# SCH_Token_Function.net
KiCad netlist of a schematic drawn in EasyEDA
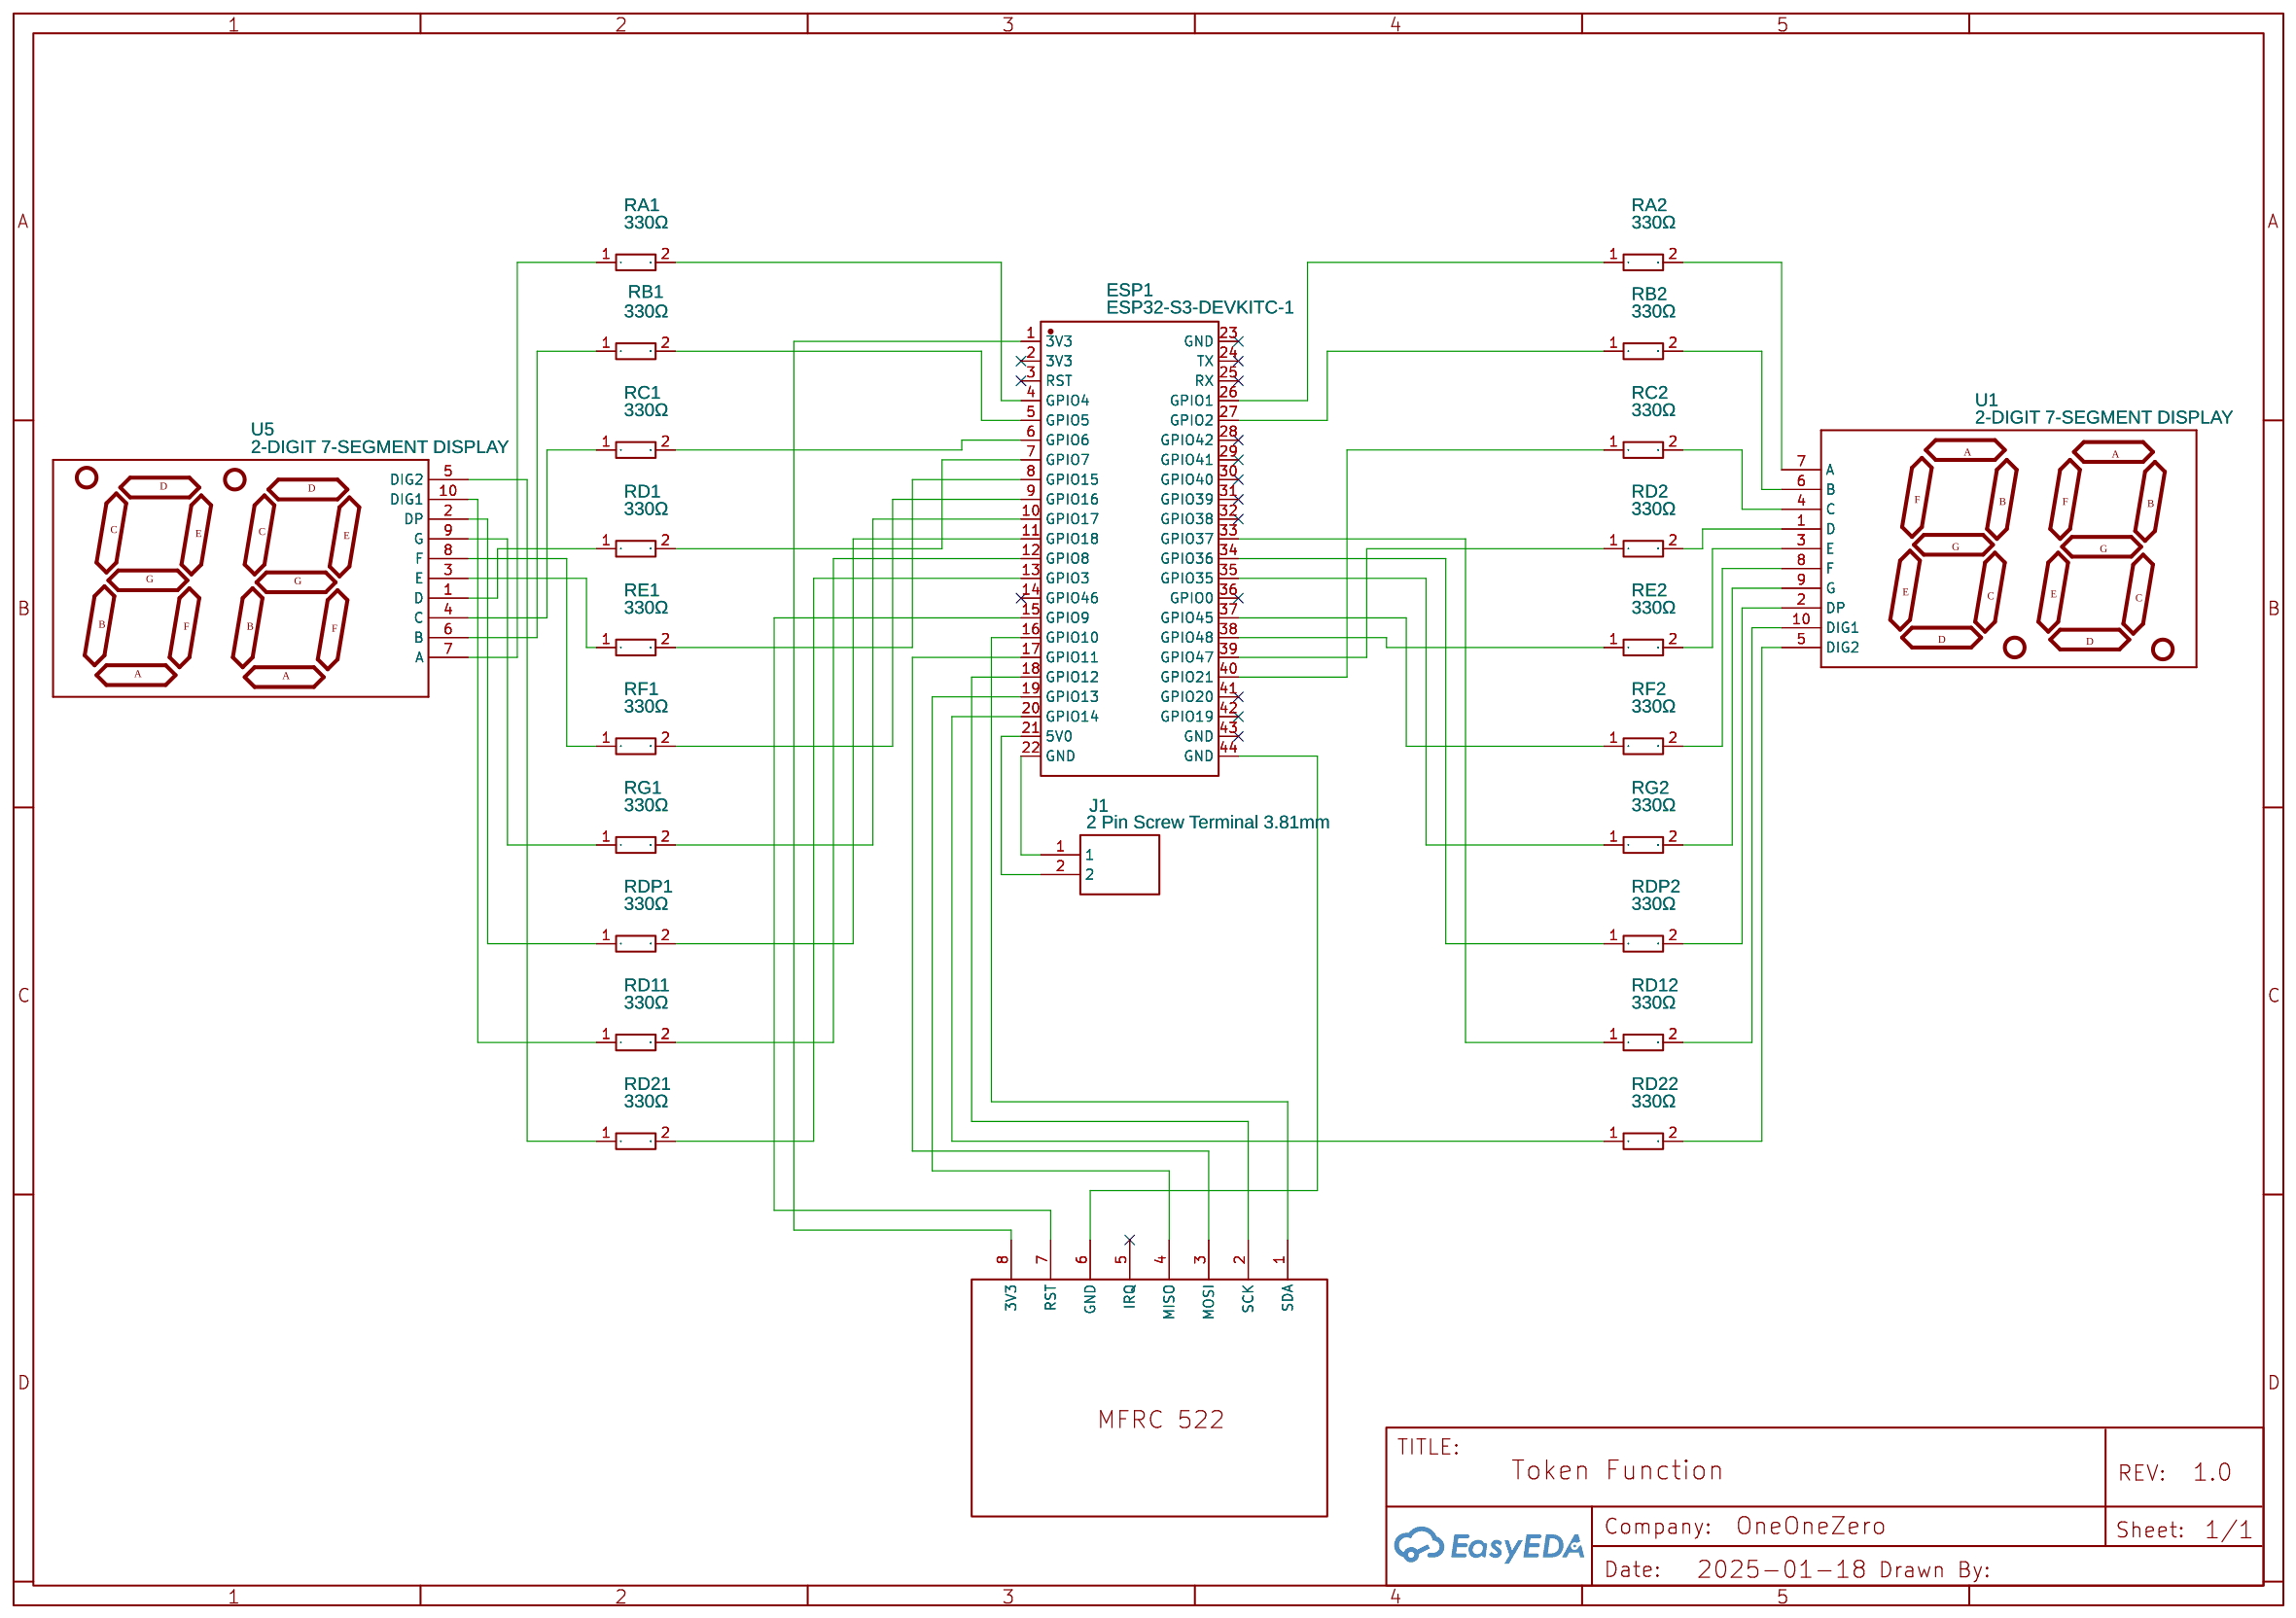
[diagram p0: schematic sheet]

(export (version "E")
  (design (tool "Eeschema 10.0.6"))
  (components
    (comp (ref "ESP1") (value "ESP32-S3-DEVKITC-1") (libsource (lib "") (part "ESP32-S3-DEVKITC-1")))
    (comp (ref "J1")
      (value "2 Pin Screw Terminal 3.81mm")
      (libsource (lib "") (part "2 Pin Screw Terminal 3.81mm"))
    )
    (comp (ref "RA1")
      (value "330Ω")
      (fields (field (name "Manufacturer Part") "MF1/4W-330Ω±1% T") (field (name "Manufacturer") "CCO(千志电子)"))
      (libsource (lib "") (part "V2-330Ω-THROUGH-HOLE-RESISTORS-5%-1/4W-D2.3-L6.5MM_3"))
    )
    (comp (ref "RA2")
      (value "330Ω")
      (fields (field (name "Manufacturer Part") "MF1/4W-330Ω±1% T") (field (name "Manufacturer") "CCO(千志电子)"))
      (libsource (lib "") (part "V2-330Ω-THROUGH-HOLE-RESISTORS-5%-1/4W-D2.3-L6.5MM_3"))
    )
    (comp (ref "RB1")
      (value "330Ω")
      (fields (field (name "Manufacturer Part") "MF1/4W-330Ω±1% T") (field (name "Manufacturer") "CCO(千志电子)"))
      (libsource (lib "") (part "V2-330Ω-THROUGH-HOLE-RESISTORS-5%-1/4W-D2.3-L6.5MM_6"))
    )
    (comp (ref "RB2")
      (value "330Ω")
      (fields (field (name "Manufacturer Part") "MF1/4W-330Ω±1% T") (field (name "Manufacturer") "CCO(千志电子)"))
      (libsource (lib "") (part "V2-330Ω-THROUGH-HOLE-RESISTORS-5%-1/4W-D2.3-L6.5MM_6"))
    )
    (comp (ref "RC1")
      (value "330Ω")
      (fields (field (name "Manufacturer Part") "MF1/4W-330Ω±1% T") (field (name "Manufacturer") "CCO(千志电子)"))
      (libsource (lib "") (part "V2-330Ω-THROUGH-HOLE-RESISTORS-5%-1/4W-D2.3-L6.5MM_5"))
    )
    (comp (ref "RC2")
      (value "330Ω")
      (fields (field (name "Manufacturer Part") "MF1/4W-330Ω±1% T") (field (name "Manufacturer") "CCO(千志电子)"))
      (libsource (lib "") (part "V2-330Ω-THROUGH-HOLE-RESISTORS-5%-1/4W-D2.3-L6.5MM_5"))
    )
    (comp (ref "RD1")
      (value "330Ω")
      (fields (field (name "Manufacturer Part") "MF1/4W-330Ω±1% T") (field (name "Manufacturer") "CCO(千志电子)"))
      (libsource (lib "") (part "V2-330Ω-THROUGH-HOLE-RESISTORS-5%-1/4W-D2.3-L6.5MM_2"))
    )
    (comp (ref "RD2")
      (value "330Ω")
      (fields (field (name "Manufacturer Part") "MF1/4W-330Ω±1% T") (field (name "Manufacturer") "CCO(千志电子)"))
      (libsource (lib "") (part "V2-330Ω-THROUGH-HOLE-RESISTORS-5%-1/4W-D2.3-L6.5MM_2"))
    )
    (comp (ref "RD11")
      (value "330Ω")
      (fields (field (name "Manufacturer Part") "MF1/4W-330Ω±1% T") (field (name "Manufacturer") "CCO(千志电子)"))
      (libsource (lib "") (part "V2-330Ω-THROUGH-HOLE-RESISTORS-5%-1/4W-D2.3-L6.5MM_2"))
    )
    (comp (ref "RD12")
      (value "330Ω")
      (fields (field (name "Manufacturer Part") "MF1/4W-330Ω±1% T") (field (name "Manufacturer") "CCO(千志电子)"))
      (libsource (lib "") (part "V2-330Ω-THROUGH-HOLE-RESISTORS-5%-1/4W-D2.3-L6.5MM_2"))
    )
    (comp (ref "RD21")
      (value "330Ω")
      (fields (field (name "Manufacturer Part") "MF1/4W-330Ω±1% T") (field (name "Manufacturer") "CCO(千志电子)"))
      (libsource (lib "") (part "V2-330Ω-THROUGH-HOLE-RESISTORS-5%-1/4W-D2.3-L6.5MM_2"))
    )
    (comp (ref "RD22")
      (value "330Ω")
      (fields (field (name "Manufacturer Part") "MF1/4W-330Ω±1% T") (field (name "Manufacturer") "CCO(千志电子)"))
      (libsource (lib "") (part "V2-330Ω-THROUGH-HOLE-RESISTORS-5%-1/4W-D2.3-L6.5MM_2"))
    )
    (comp (ref "RDP1")
      (value "330Ω")
      (fields (field (name "Manufacturer Part") "MF1/4W-330Ω±1% T") (field (name "Manufacturer") "CCO(千志电子)"))
      (libsource (lib "") (part "V2-330Ω-THROUGH-HOLE-RESISTORS-5%-1/4W-D2.3-L6.5MM_7"))
    )
    (comp (ref "RDP2")
      (value "330Ω")
      (fields (field (name "Manufacturer Part") "MF1/4W-330Ω±1% T") (field (name "Manufacturer") "CCO(千志电子)"))
      (libsource (lib "") (part "V2-330Ω-THROUGH-HOLE-RESISTORS-5%-1/4W-D2.3-L6.5MM_7"))
    )
    (comp (ref "RE1")
      (value "330Ω")
      (fields (field (name "Manufacturer Part") "MF1/4W-330Ω±1% T") (field (name "Manufacturer") "CCO(千志电子)"))
      (libsource (lib "") (part "V2-330Ω-THROUGH-HOLE-RESISTORS-5%-1/4W-D2.3-L6.5MM_4"))
    )
    (comp (ref "RE2")
      (value "330Ω")
      (fields (field (name "Manufacturer Part") "MF1/4W-330Ω±1% T") (field (name "Manufacturer") "CCO(千志电子)"))
      (libsource (lib "") (part "V2-330Ω-THROUGH-HOLE-RESISTORS-5%-1/4W-D2.3-L6.5MM_4"))
    )
    (comp (ref "RF1")
      (value "330Ω")
      (fields (field (name "Manufacturer Part") "MF1/4W-330Ω±1% T") (field (name "Manufacturer") "CCO(千志电子)"))
      (libsource (lib "") (part "V2-330Ω-THROUGH-HOLE-RESISTORS-5%-1/4W-D2.3-L6.5MM"))
    )
    (comp (ref "RF2")
      (value "330Ω")
      (fields (field (name "Manufacturer Part") "MF1/4W-330Ω±1% T") (field (name "Manufacturer") "CCO(千志电子)"))
      (libsource (lib "") (part "V2-330Ω-THROUGH-HOLE-RESISTORS-5%-1/4W-D2.3-L6.5MM"))
    )
    (comp (ref "RG1")
      (value "330Ω")
      (fields (field (name "Manufacturer Part") "MF1/4W-330Ω±1% T") (field (name "Manufacturer") "CCO(千志电子)"))
      (libsource (lib "") (part "V2-330Ω-THROUGH-HOLE-RESISTORS-5%-1/4W-D2.3-L6.5MM_1"))
    )
    (comp (ref "RG2")
      (value "330Ω")
      (fields (field (name "Manufacturer Part") "MF1/4W-330Ω±1% T") (field (name "Manufacturer") "CCO(千志电子)"))
      (libsource (lib "") (part "V2-330Ω-THROUGH-HOLE-RESISTORS-5%-1/4W-D2.3-L6.5MM_1"))
    )
    (comp (ref "U1")
      (value "2-DIGIT 7-SEGMENT DISPLAY")
      (libsource (lib "") (part "2-DIGIT 7-SEGMENT DISPLAY"))
    )
    (comp (ref "U2") (value "MFRC522-MODULE-FLIPPED") (libsource (lib "") (part "MFRC522-MODULE-FLIPPED")))
    (comp (ref "U5")
      (value "2-DIGIT 7-SEGMENT DISPLAY")
      (libsource (lib "") (part "2-DIGIT 7-SEGMENT DISPLAY_1"))
    )
  )
  (nets
    (net (code "1") (name "Net-(ESP1-5V0)") (class "Default")
      (node (ref "ESP1") (pin "21") (pinfunction "5V0_21") (pintype "unspecified"))
      (node (ref "J1") (pin "2") (pinfunction "2_2") (pintype "unspecified"))
    )
    (net (code "2") (name "Net-(ESP1-GND-Pad22)") (class "Default")
      (node (ref "ESP1") (pin "22") (pinfunction "GND_22") (pintype "unspecified"))
      (node (ref "J1") (pin "1") (pinfunction "1_1") (pintype "unspecified"))
    )
    (net (code "3") (name "Net-(ESP1-GPIO1)") (class "Default")
      (node (ref "ESP1") (pin "26") (pinfunction "GPIO1_26") (pintype "unspecified"))
      (node (ref "RA2") (pin "1") (pinfunction "1_1") (pintype "unspecified"))
    )
    (net (code "4") (name "Net-(ESP1-GPIO2)") (class "Default")
      (node (ref "ESP1") (pin "27") (pinfunction "GPIO2_27") (pintype "unspecified"))
      (node (ref "RB2") (pin "1") (pinfunction "1_1") (pintype "unspecified"))
    )
    (net (code "5") (name "Net-(ESP1-GPIO3)") (class "Default")
      (node (ref "ESP1") (pin "13") (pinfunction "GPIO3_13") (pintype "unspecified"))
      (node (ref "RD21") (pin "2") (pinfunction "2_2") (pintype "unspecified"))
    )
    (net (code "6") (name "Net-(ESP1-GPIO4)") (class "Default")
      (node (ref "ESP1") (pin "4") (pinfunction "GPIO4_4") (pintype "unspecified"))
      (node (ref "RA1") (pin "2") (pinfunction "2_2") (pintype "unspecified"))
    )
    (net (code "7") (name "Net-(ESP1-GPIO5)") (class "Default")
      (node (ref "ESP1") (pin "5") (pinfunction "GPIO5_5") (pintype "unspecified"))
      (node (ref "RB1") (pin "2") (pinfunction "2_2") (pintype "unspecified"))
    )
    (net (code "8") (name "Net-(ESP1-GPIO6)") (class "Default")
      (node (ref "ESP1") (pin "6") (pinfunction "GPIO6_6") (pintype "unspecified"))
      (node (ref "RC1") (pin "2") (pinfunction "2_2") (pintype "unspecified"))
    )
    (net (code "9") (name "Net-(ESP1-GPIO7)") (class "Default")
      (node (ref "ESP1") (pin "7") (pinfunction "GPIO7_7") (pintype "unspecified"))
      (node (ref "RD1") (pin "2") (pinfunction "2_2") (pintype "unspecified"))
    )
    (net (code "10") (name "Net-(ESP1-GPIO8)") (class "Default")
      (node (ref "ESP1") (pin "12") (pinfunction "GPIO8_12") (pintype "unspecified"))
      (node (ref "RD11") (pin "2") (pinfunction "2_2") (pintype "unspecified"))
    )
    (net (code "11") (name "Net-(ESP1-GPIO9)") (class "Default")
      (node (ref "ESP1") (pin "15") (pinfunction "GPIO9_15") (pintype "unspecified"))
      (node (ref "U2") (pin "7") (pinfunction "RST_7") (pintype "unspecified"))
    )
    (net (code "12") (name "Net-(ESP1-GPIO10)") (class "Default")
      (node (ref "ESP1") (pin "16") (pinfunction "GPIO10_16") (pintype "unspecified"))
      (node (ref "U2") (pin "1") (pinfunction "SDA_1") (pintype "unspecified"))
    )
    (net (code "13") (name "Net-(ESP1-GPIO11)") (class "Default")
      (node (ref "ESP1") (pin "17") (pinfunction "GPIO11_17") (pintype "unspecified"))
      (node (ref "U2") (pin "3") (pinfunction "MOSI_3") (pintype "unspecified"))
    )
    (net (code "14") (name "Net-(ESP1-GPIO12)") (class "Default")
      (node (ref "ESP1") (pin "18") (pinfunction "GPIO12_18") (pintype "unspecified"))
      (node (ref "U2") (pin "2") (pinfunction "SCK_2") (pintype "unspecified"))
    )
    (net (code "15") (name "Net-(ESP1-GPIO13)") (class "Default")
      (node (ref "ESP1") (pin "19") (pinfunction "GPIO13_19") (pintype "unspecified"))
      (node (ref "U2") (pin "4") (pinfunction "MISO_4") (pintype "unspecified"))
    )
    (net (code "16") (name "Net-(ESP1-GPIO14)") (class "Default")
      (node (ref "ESP1") (pin "20") (pinfunction "GPIO14_20") (pintype "unspecified"))
      (node (ref "RD22") (pin "1") (pinfunction "1_1") (pintype "unspecified"))
    )
    (net (code "17") (name "Net-(ESP1-GPIO15)") (class "Default")
      (node (ref "ESP1") (pin "8") (pinfunction "GPIO15_8") (pintype "unspecified"))
      (node (ref "RE1") (pin "2") (pinfunction "2_2") (pintype "unspecified"))
    )
    (net (code "18") (name "Net-(ESP1-GPIO16)") (class "Default")
      (node (ref "ESP1") (pin "9") (pinfunction "GPIO16_9") (pintype "unspecified"))
      (node (ref "RF1") (pin "2") (pinfunction "2_2") (pintype "unspecified"))
    )
    (net (code "19") (name "Net-(ESP1-GPIO17)") (class "Default")
      (node (ref "ESP1") (pin "10") (pinfunction "GPIO17_10") (pintype "unspecified"))
      (node (ref "RG1") (pin "2") (pinfunction "2_2") (pintype "unspecified"))
    )
    (net (code "20") (name "Net-(ESP1-GPIO18)") (class "Default")
      (node (ref "ESP1") (pin "11") (pinfunction "GPIO18_11") (pintype "unspecified"))
      (node (ref "RDP1") (pin "2") (pinfunction "2_2") (pintype "unspecified"))
    )
    (net (code "21") (name "Net-(ESP1-GPIO21)") (class "Default")
      (node (ref "ESP1") (pin "40") (pinfunction "GPIO21_40") (pintype "unspecified"))
      (node (ref "RC2") (pin "1") (pinfunction "1_1") (pintype "unspecified"))
    )
    (net (code "22") (name "Net-(ESP1-GPIO35)") (class "Default")
      (node (ref "ESP1") (pin "35") (pinfunction "GPIO35_35") (pintype "unspecified"))
      (node (ref "RG2") (pin "1") (pinfunction "1_1") (pintype "unspecified"))
    )
    (net (code "23") (name "Net-(ESP1-GPIO36)") (class "Default")
      (node (ref "ESP1") (pin "34") (pinfunction "GPIO36_34") (pintype "unspecified"))
      (node (ref "RDP2") (pin "1") (pinfunction "1_1") (pintype "unspecified"))
    )
    (net (code "24") (name "Net-(ESP1-GPIO37)") (class "Default")
      (node (ref "ESP1") (pin "33") (pinfunction "GPIO37_33") (pintype "unspecified"))
      (node (ref "RD12") (pin "1") (pinfunction "1_1") (pintype "unspecified"))
    )
    (net (code "25") (name "Net-(ESP1-GPIO45)") (class "Default")
      (node (ref "ESP1") (pin "37") (pinfunction "GPIO45_37") (pintype "unspecified"))
      (node (ref "RF2") (pin "1") (pinfunction "1_1") (pintype "unspecified"))
    )
    (net (code "26") (name "Net-(ESP1-GPIO47)") (class "Default")
      (node (ref "ESP1") (pin "39") (pinfunction "GPIO47_39") (pintype "unspecified"))
      (node (ref "RD2") (pin "1") (pinfunction "1_1") (pintype "unspecified"))
    )
    (net (code "27") (name "Net-(ESP1-GPIO48)") (class "Default")
      (node (ref "ESP1") (pin "38") (pinfunction "GPIO48_38") (pintype "unspecified"))
      (node (ref "RE2") (pin "1") (pinfunction "1_1") (pintype "unspecified"))
    )
    (net (code "28") (name "Net-(U1-A)") (class "Default")
      (node (ref "RA2") (pin "2") (pinfunction "2_2") (pintype "unspecified"))
      (node (ref "U1") (pin "7") (pinfunction "A_7") (pintype "unspecified"))
    )
    (net (code "29") (name "Net-(U1-B)") (class "Default")
      (node (ref "RB2") (pin "2") (pinfunction "2_2") (pintype "unspecified"))
      (node (ref "U1") (pin "6") (pinfunction "B_6") (pintype "unspecified"))
    )
    (net (code "30") (name "Net-(U1-C)") (class "Default")
      (node (ref "RC2") (pin "2") (pinfunction "2_2") (pintype "unspecified"))
      (node (ref "U1") (pin "4") (pinfunction "C_4") (pintype "unspecified"))
    )
    (net (code "31") (name "Net-(U1-D)") (class "Default")
      (node (ref "RD2") (pin "2") (pinfunction "2_2") (pintype "unspecified"))
      (node (ref "U1") (pin "1") (pinfunction "D_1") (pintype "unspecified"))
    )
    (net (code "32") (name "Net-(U1-DIG1)") (class "Default")
      (node (ref "RD12") (pin "2") (pinfunction "2_2") (pintype "unspecified"))
      (node (ref "U1") (pin "10") (pinfunction "DIG1_10") (pintype "unspecified"))
    )
    (net (code "33") (name "Net-(U1-DIG2)") (class "Default")
      (node (ref "RD22") (pin "2") (pinfunction "2_2") (pintype "unspecified"))
      (node (ref "U1") (pin "5") (pinfunction "DIG2_5") (pintype "unspecified"))
    )
    (net (code "34") (name "Net-(U1-DP)") (class "Default")
      (node (ref "RDP2") (pin "2") (pinfunction "2_2") (pintype "unspecified"))
      (node (ref "U1") (pin "2") (pinfunction "DP_2") (pintype "unspecified"))
    )
    (net (code "35") (name "Net-(U1-E)") (class "Default")
      (node (ref "RE2") (pin "2") (pinfunction "2_2") (pintype "unspecified"))
      (node (ref "U1") (pin "3") (pinfunction "E_3") (pintype "unspecified"))
    )
    (net (code "36") (name "Net-(U1-F)") (class "Default")
      (node (ref "RF2") (pin "2") (pinfunction "2_2") (pintype "unspecified"))
      (node (ref "U1") (pin "8") (pinfunction "F_8") (pintype "unspecified"))
    )
    (net (code "37") (name "Net-(U1-G)") (class "Default")
      (node (ref "RG2") (pin "2") (pinfunction "2_2") (pintype "unspecified"))
      (node (ref "U1") (pin "9") (pinfunction "G_9") (pintype "unspecified"))
    )
    (net (code "38") (name "Net-(U2-3V3)") (class "Default")
      (node (ref "ESP1") (pin "1") (pinfunction "3V3_1") (pintype "unspecified"))
      (node (ref "U2") (pin "8") (pinfunction "3V3_8") (pintype "unspecified"))
    )
    (net (code "39") (name "Net-(U2-GND)") (class "Default")
      (node (ref "ESP1") (pin "44") (pinfunction "GND_44") (pintype "unspecified"))
      (node (ref "U2") (pin "6") (pinfunction "GND_6") (pintype "unspecified"))
    )
    (net (code "40") (name "Net-(U5-A)") (class "Default")
      (node (ref "RA1") (pin "1") (pinfunction "1_1") (pintype "unspecified"))
      (node (ref "U5") (pin "7") (pinfunction "A_7") (pintype "unspecified"))
    )
    (net (code "41") (name "Net-(U5-B)") (class "Default")
      (node (ref "RB1") (pin "1") (pinfunction "1_1") (pintype "unspecified"))
      (node (ref "U5") (pin "6") (pinfunction "B_6") (pintype "unspecified"))
    )
    (net (code "42") (name "Net-(U5-C)") (class "Default")
      (node (ref "RC1") (pin "1") (pinfunction "1_1") (pintype "unspecified"))
      (node (ref "U5") (pin "4") (pinfunction "C_4") (pintype "unspecified"))
    )
    (net (code "43") (name "Net-(U5-D)") (class "Default")
      (node (ref "RD1") (pin "1") (pinfunction "1_1") (pintype "unspecified"))
      (node (ref "U5") (pin "1") (pinfunction "D_1") (pintype "unspecified"))
    )
    (net (code "44") (name "Net-(U5-DIG1)") (class "Default")
      (node (ref "RD11") (pin "1") (pinfunction "1_1") (pintype "unspecified"))
      (node (ref "U5") (pin "10") (pinfunction "DIG1_10") (pintype "unspecified"))
    )
    (net (code "45") (name "Net-(U5-DIG2)") (class "Default")
      (node (ref "RD21") (pin "1") (pinfunction "1_1") (pintype "unspecified"))
      (node (ref "U5") (pin "5") (pinfunction "DIG2_5") (pintype "unspecified"))
    )
    (net (code "46") (name "Net-(U5-DP)") (class "Default")
      (node (ref "RDP1") (pin "1") (pinfunction "1_1") (pintype "unspecified"))
      (node (ref "U5") (pin "2") (pinfunction "DP_2") (pintype "unspecified"))
    )
    (net (code "47") (name "Net-(U5-E)") (class "Default")
      (node (ref "RE1") (pin "1") (pinfunction "1_1") (pintype "unspecified"))
      (node (ref "U5") (pin "3") (pinfunction "E_3") (pintype "unspecified"))
    )
    (net (code "48") (name "Net-(U5-F)") (class "Default")
      (node (ref "RF1") (pin "1") (pinfunction "1_1") (pintype "unspecified"))
      (node (ref "U5") (pin "8") (pinfunction "F_8") (pintype "unspecified"))
    )
    (net (code "49") (name "Net-(U5-G)") (class "Default")
      (node (ref "RG1") (pin "1") (pinfunction "1_1") (pintype "unspecified"))
      (node (ref "U5") (pin "9") (pinfunction "G_9") (pintype "unspecified"))
    )
    (net (code "50") (name "unconnected-(ESP1-3V3-Pad2)") (class "Default")
      (node (ref "ESP1") (pin "2") (pinfunction "3V3_2") (pintype "unspecified+no_connect"))
    )
    (net (code "51") (name "unconnected-(ESP1-GND-Pad23)") (class "Default")
      (node (ref "ESP1") (pin "23") (pinfunction "GND_23") (pintype "unspecified+no_connect"))
    )
    (net (code "52") (name "unconnected-(ESP1-GND-Pad43)") (class "Default")
      (node (ref "ESP1") (pin "43") (pinfunction "GND_43") (pintype "unspecified+no_connect"))
    )
    (net (code "53") (name "unconnected-(ESP1-GPIO0-Pad36)") (class "Default")
      (node (ref "ESP1") (pin "36") (pinfunction "GPIO0_36") (pintype "unspecified+no_connect"))
    )
    (net (code "54") (name "unconnected-(ESP1-GPIO19-Pad42)") (class "Default")
      (node (ref "ESP1") (pin "42") (pinfunction "GPIO19_42") (pintype "unspecified+no_connect"))
    )
    (net (code "55") (name "unconnected-(ESP1-GPIO20-Pad41)") (class "Default")
      (node (ref "ESP1") (pin "41") (pinfunction "GPIO20_41") (pintype "unspecified+no_connect"))
    )
    (net (code "56") (name "unconnected-(ESP1-GPIO38-Pad32)") (class "Default")
      (node (ref "ESP1") (pin "32") (pinfunction "GPIO38_32") (pintype "unspecified+no_connect"))
    )
    (net (code "57") (name "unconnected-(ESP1-GPIO39-Pad31)") (class "Default")
      (node (ref "ESP1") (pin "31") (pinfunction "GPIO39_31") (pintype "unspecified+no_connect"))
    )
    (net (code "58") (name "unconnected-(ESP1-GPIO40-Pad30)") (class "Default")
      (node (ref "ESP1") (pin "30") (pinfunction "GPIO40_30") (pintype "unspecified+no_connect"))
    )
    (net (code "59") (name "unconnected-(ESP1-GPIO41-Pad29)") (class "Default")
      (node (ref "ESP1") (pin "29") (pinfunction "GPIO41_29") (pintype "unspecified+no_connect"))
    )
    (net (code "60") (name "unconnected-(ESP1-GPIO42-Pad28)") (class "Default")
      (node (ref "ESP1") (pin "28") (pinfunction "GPIO42_28") (pintype "unspecified+no_connect"))
    )
    (net (code "61") (name "unconnected-(ESP1-GPIO46-Pad14)") (class "Default")
      (node (ref "ESP1") (pin "14") (pinfunction "GPIO46_14") (pintype "unspecified+no_connect"))
    )
    (net (code "62") (name "unconnected-(ESP1-RST-Pad3)") (class "Default")
      (node (ref "ESP1") (pin "3") (pinfunction "RST_3") (pintype "unspecified+no_connect"))
    )
    (net (code "63") (name "unconnected-(ESP1-RX-Pad25)") (class "Default")
      (node (ref "ESP1") (pin "25") (pinfunction "RX_25") (pintype "unspecified+no_connect"))
    )
    (net (code "64") (name "unconnected-(ESP1-TX-Pad24)") (class "Default")
      (node (ref "ESP1") (pin "24") (pinfunction "TX_24") (pintype "unspecified+no_connect"))
    )
    (net (code "65") (name "unconnected-(U2-IRQ-Pad5)") (class "Default")
      (node (ref "U2") (pin "5") (pinfunction "IRQ_5") (pintype "unspecified+no_connect"))
    )
  )
)
